# Top.net
KiCad netlist of a schematic drawn in Altium Designer
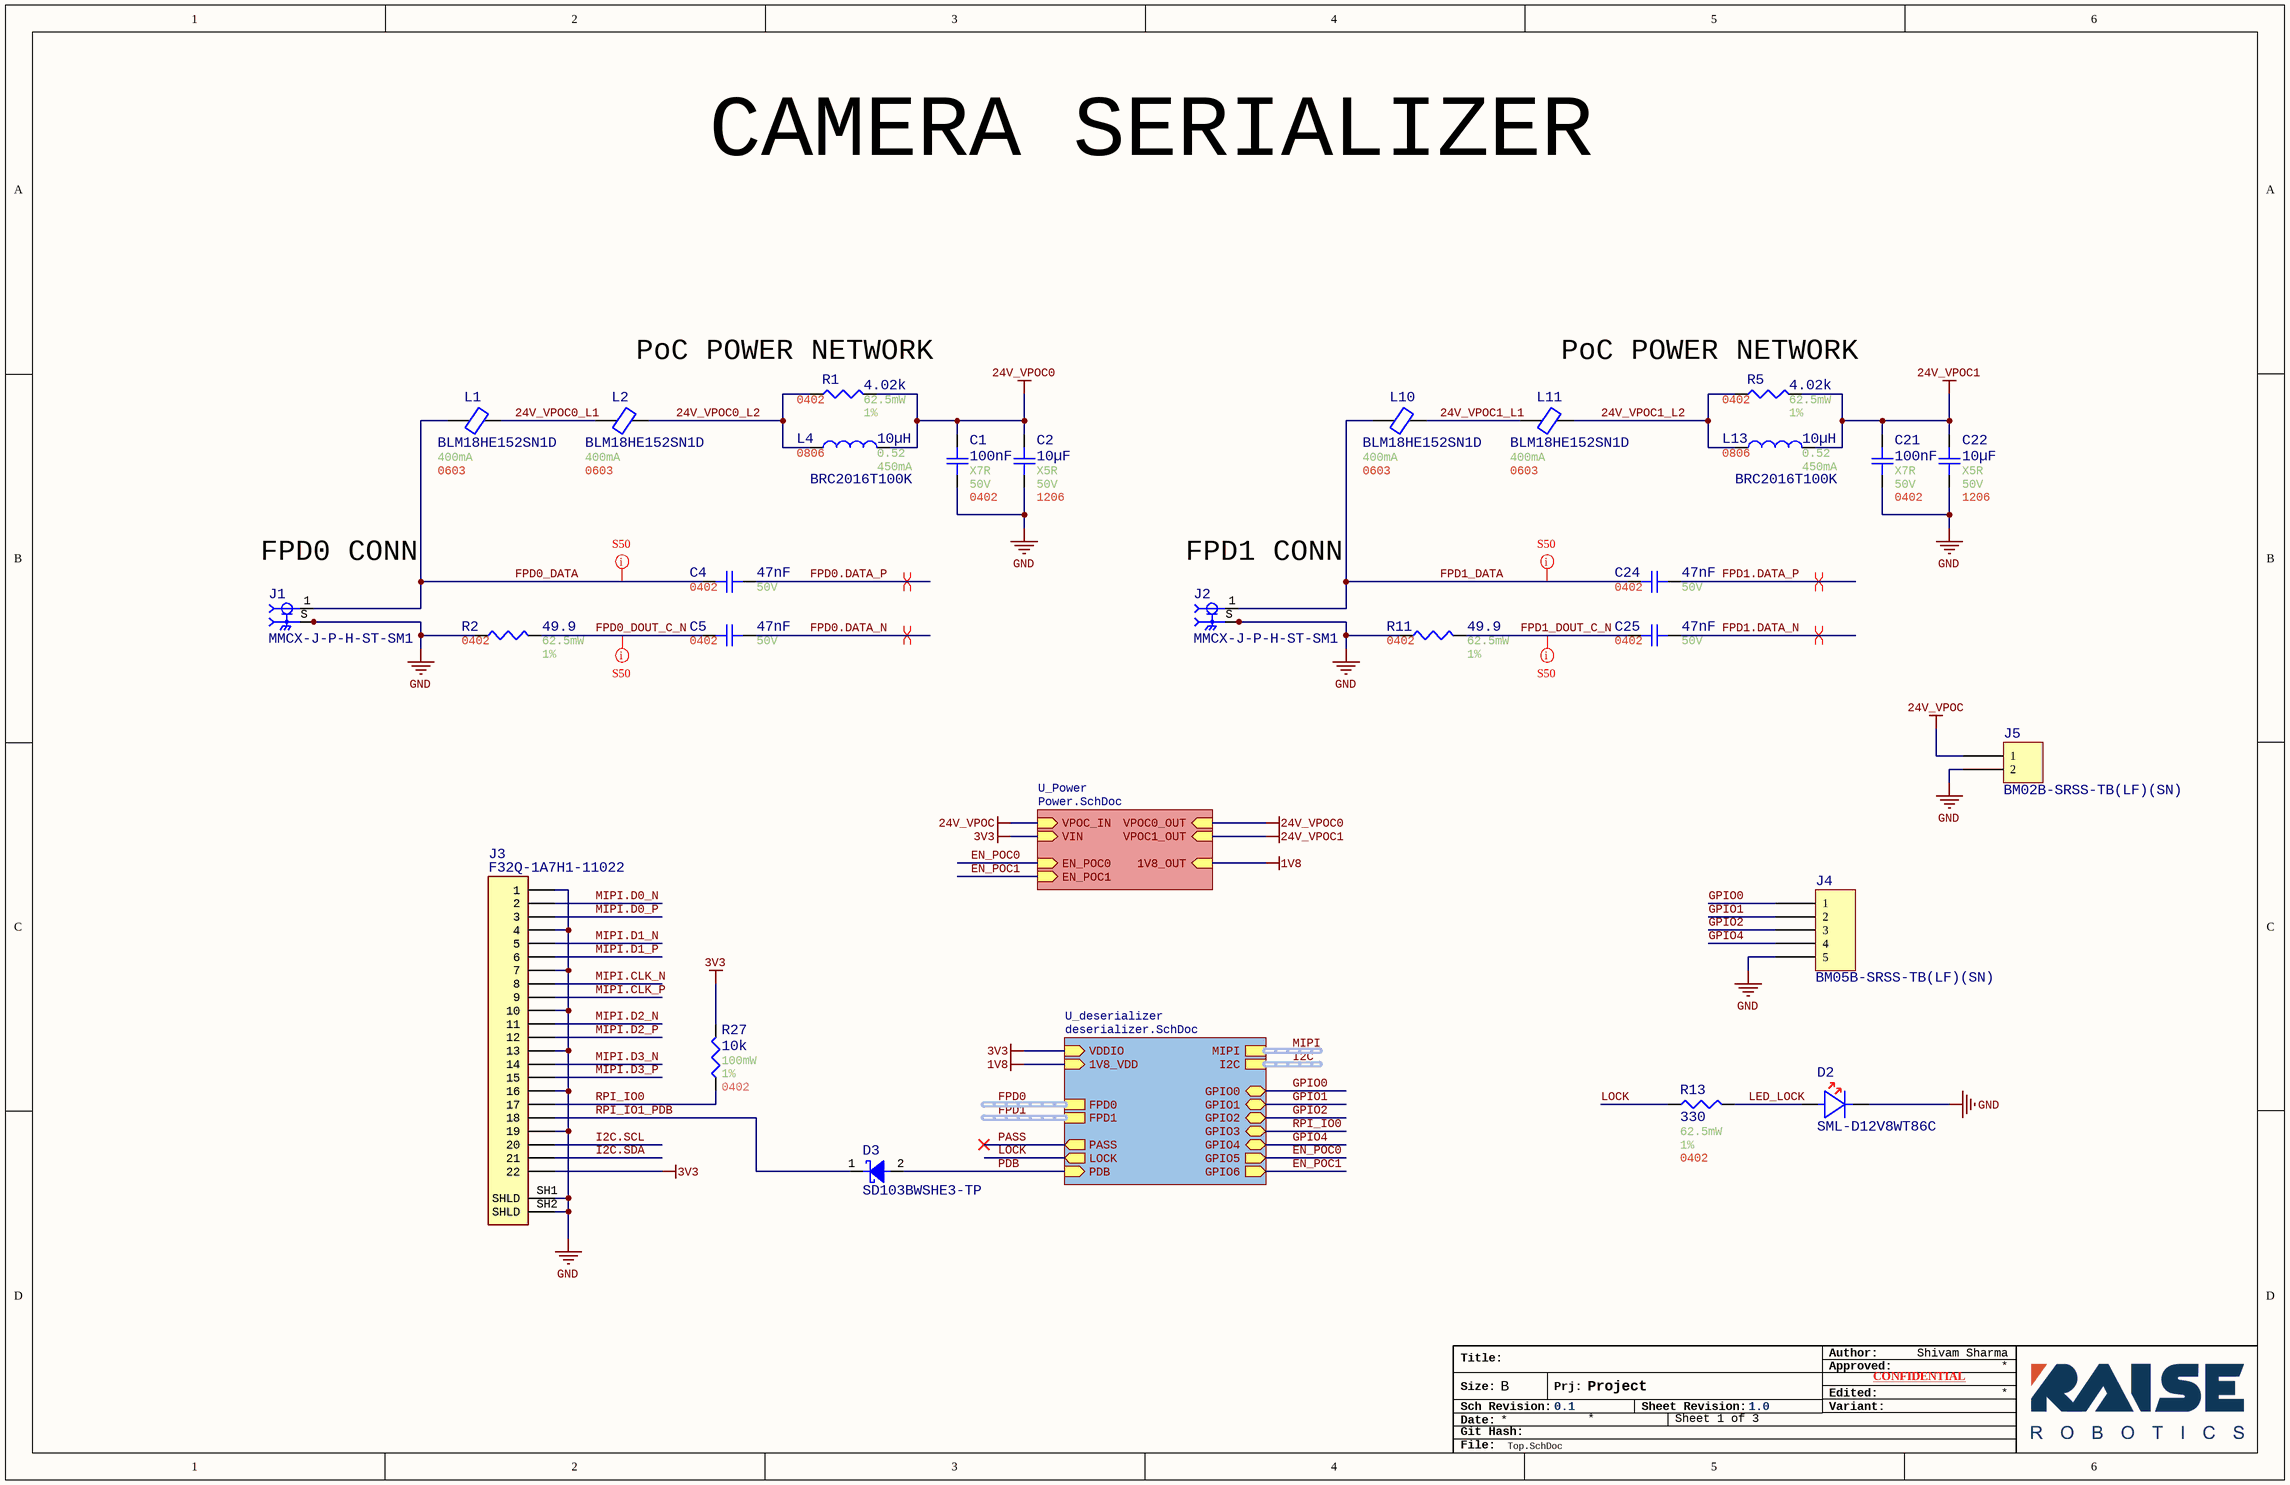
[diagram p0: Top.SchDoc]

(export (version "E")
  (design (tool "Eeschema 10.0.6"))
  (components
    (comp (ref "C1")
      (value "100nF")
      (footprint "Generic 0402 capacitor")
      (fields
        (field (name "TEMPERATURE COEFFICIENT") "X7R")
        (field (name "VOLTAGE RATING") "50V")
        (field (name "CASE/PACKAGE") "0402")
        (field (name "TOLERANCE") "10%")
        (field (name "Comment") "GRT155R71H104KE01D")
      )
      (libsource (lib "Raise Robotics") (part "Unpolarized Capacitor"))
    )
    (comp (ref "C2")
      (value "10µF")
      (footprint "Generic 1206 Capacitor")
      (fields
        (field (name "TEMPERATURE COEFFICIENT") "X5R")
        (field (name "VOLTAGE RATING") "50V")
        (field (name "CASE/PACKAGE") "1206")
        (field (name "TOLERANCE") "20%")
        (field (name "Comment") "CL31A106MBHNNNE")
      )
      (libsource (lib "Raise Robotics") (part "Unpolarized Capacitor"))
    )
    (comp (ref "C4")
      (value "47nF")
      (footprint "Generic 0402 capacitor")
      (description "50V 47nF X7R ±10% 0402 Multilayer Ceramic Capacitors MLCC - SMD/SMT ROHS")
      (fields
        (field (name "VOLTAGE RATING") "50V")
        (field (name "CASE/PACKAGE") "0402")
        (field (name "TOLERANCE") "10%")
        (field (name "Comment") "GRM155R71H473KE14D")
      )
      (libsource (lib "Raise Robotics") (part "Unpolarized Capacitor"))
    )
    (comp (ref "C5")
      (value "47nF")
      (footprint "Generic 0402 capacitor")
      (description "50V 47nF X7R ±10% 0402 Multilayer Ceramic Capacitors MLCC - SMD/SMT ROHS")
      (fields
        (field (name "VOLTAGE RATING") "50V")
        (field (name "CASE/PACKAGE") "0402")
        (field (name "TOLERANCE") "10%")
        (field (name "Comment") "GRM155R71H473KE14D")
      )
      (libsource (lib "Raise Robotics") (part "Unpolarized Capacitor"))
    )
    (comp (ref "C21")
      (value "100nF")
      (footprint "Generic 0402 capacitor")
      (fields
        (field (name "TEMPERATURE COEFFICIENT") "X7R")
        (field (name "VOLTAGE RATING") "50V")
        (field (name "CASE/PACKAGE") "0402")
        (field (name "TOLERANCE") "10%")
        (field (name "Comment") "GRT155R71H104KE01D")
      )
      (libsource (lib "Raise Robotics") (part "Unpolarized Capacitor"))
    )
    (comp (ref "C22")
      (value "10µF")
      (footprint "Generic 1206 Capacitor")
      (fields
        (field (name "TEMPERATURE COEFFICIENT") "X5R")
        (field (name "VOLTAGE RATING") "50V")
        (field (name "CASE/PACKAGE") "1206")
        (field (name "TOLERANCE") "20%")
        (field (name "Comment") "CL31A106MBHNNNE")
      )
      (libsource (lib "Raise Robotics") (part "Unpolarized Capacitor"))
    )
    (comp (ref "C24")
      (value "47nF")
      (footprint "Generic 0402 capacitor")
      (description "50V 47nF X7R ±10% 0402 Multilayer Ceramic Capacitors MLCC - SMD/SMT ROHS")
      (fields
        (field (name "VOLTAGE RATING") "50V")
        (field (name "CASE/PACKAGE") "0402")
        (field (name "TOLERANCE") "10%")
        (field (name "Comment") "GRM155R71H473KE14D")
      )
      (libsource (lib "Raise Robotics") (part "Unpolarized Capacitor"))
    )
    (comp (ref "C25")
      (value "47nF")
      (footprint "Generic 0402 capacitor")
      (description "50V 47nF X7R ±10% 0402 Multilayer Ceramic Capacitors MLCC - SMD/SMT ROHS")
      (fields
        (field (name "VOLTAGE RATING") "50V")
        (field (name "CASE/PACKAGE") "0402")
        (field (name "TOLERANCE") "10%")
        (field (name "Comment") "GRM155R71H473KE14D")
      )
      (libsource (lib "Raise Robotics") (part "Unpolarized Capacitor"))
    )
    (comp (ref "D2")
      (value "SML-D12V8WT86C")
      (footprint "FP-SML-D12-MFG")
      (description "Red 630nm LED Indication - Discrete 2.2V 0603 (1608 Metric)")
      (libsource (lib "Raise Robotics") (part "LED Red"))
    )
    (comp (ref "D3")
      (value "SD103BWSHE3-TP")
      (footprint "SOD-323")
      (description "Rectifier Diode, Schottky, 1 Phase, 1 Element, 0.35A, 30V V(RRM), Silicon")
      (libsource (lib "Raise Robotics") (part "Generic 2 pin Diode"))
    )
    (comp (ref "J1")
      (value "MMCX-J-P-H-ST-SM1")
      (footprint "MMCX-J-P-H-ST-SM1")
      (description "RF / Coaxial Connector, MMCX Coaxial, Straight Jack, Surface Mount Vertical, 50 ohm")
      (fields (field (name "MANUFACTURER") "Samtec"))
      (libsource (lib "Raise Robotics") (part "RF 1pin + 4 shield"))
    )
    (comp (ref "J2")
      (value "MMCX-J-P-H-ST-SM1")
      (footprint "MMCX-J-P-H-ST-SM1")
      (description "RF / Coaxial Connector, MMCX Coaxial, Straight Jack, Surface Mount Vertical, 50 ohm")
      (fields (field (name "MANUFACTURER") "Samtec"))
      (libsource (lib "Raise Robotics") (part "RF 1pin + 4 shield"))
    )
    (comp (ref "J3")
      (value "F32Q-1A7H1-11022")
      (footprint "F32Q-1A7H1-11022")
      (description "FPC/FFC Connector Socket 22 Position 0.5mm Top Contact Solder Right Angle Surface Mount T/R")
      (fields (field (name "MANUFACTURER") "Amphenol"))
      (libsource (lib "Raise Robotics") (part "F32Q-1A7H1-11022"))
    )
    (comp (ref "J4")
      (value "BM05B-SRSS-TB(LF)(SN)")
      (footprint "JST BM05B-SRSS-TB")
      (description "CONN HEADER SMD 5POS 1MM")
      (fields (field (name "MANUFACTURER") "JST Sales America Inc."))
      (libsource (lib "Celestial Altium Library - altium_library") (part "5 Pin"))
    )
    (comp (ref "J5")
      (value "BM02B-SRSS-TB(LF)(SN)")
      (footprint "JST BM02B-SRSS-TB")
      (description "CONN HEADER SMD 2POS 1MM")
      (fields (field (name "MANUFACTURER") "JST Sales America Inc."))
      (libsource (lib "Celestial Altium Library - altium_library") (part "2 Pin"))
    )
    (comp (ref "L1")
      (value "BLM18HE152SN1D")
      (footprint "0603_1.6x0.8x0.8mm_IND")
      (description "Ferrite Beads Multi-Layer 1.5KOhm 25% 100MHz 500mA 500mOhm DCR 0603 T/R")
      (fields
        (field (name "CURRENT RATING") "400mA")
        (field (name "CASE/PACKAGE") "0603")
        (field (name "TOLERANCE") "25%")
      )
      (libsource (lib "Raise Robotics") (part "Generic 2 pin ferrite bead"))
    )
    (comp (ref "L2")
      (value "BLM18HE152SN1D")
      (footprint "0603_1.6x0.8x0.8mm_IND")
      (description "Ferrite Beads Multi-Layer 1.5KOhm 25% 100MHz 500mA 500mOhm DCR 0603 T/R")
      (fields
        (field (name "CURRENT RATING") "400mA")
        (field (name "CASE/PACKAGE") "0603")
        (field (name "TOLERANCE") "25%")
      )
      (libsource (lib "Raise Robotics") (part "Generic 2 pin ferrite bead"))
    )
    (comp (ref "L4")
      (value "BRC2016T100K")
      (footprint "0805_2.0x1.6x1.6mm_IND")
      (description "IND 10UH 20% 3.1A SHD")
      (fields
        (field (name "DCR") "0.52")
        (field (name "CURRENT RATING") "450mA")
        (field (name "CASE/PACKAGE") "0806")
        (field (name "ALTIUM_VALUE") "10µH")
        (field (name "TOLERANCE") "10%")
      )
      (libsource (lib "Raise Robotics") (part "Generic 2 pin inductor"))
    )
    (comp (ref "L10")
      (value "BLM18HE152SN1D")
      (footprint "0603_1.6x0.8x0.8mm_IND")
      (description "Ferrite Beads Multi-Layer 1.5KOhm 25% 100MHz 500mA 500mOhm DCR 0603 T/R")
      (fields
        (field (name "CURRENT RATING") "400mA")
        (field (name "CASE/PACKAGE") "0603")
        (field (name "TOLERANCE") "25%")
      )
      (libsource (lib "Raise Robotics") (part "Generic 2 pin ferrite bead"))
    )
    (comp (ref "L11")
      (value "BLM18HE152SN1D")
      (footprint "0603_1.6x0.8x0.8mm_IND")
      (description "Ferrite Beads Multi-Layer 1.5KOhm 25% 100MHz 500mA 500mOhm DCR 0603 T/R")
      (fields
        (field (name "CURRENT RATING") "400mA")
        (field (name "CASE/PACKAGE") "0603")
        (field (name "TOLERANCE") "25%")
      )
      (libsource (lib "Raise Robotics") (part "Generic 2 pin ferrite bead"))
    )
    (comp (ref "L13")
      (value "BRC2016T100K")
      (footprint "0805_2.0x1.6x1.6mm_IND")
      (description "IND 10UH 20% 3.1A SHD")
      (fields
        (field (name "DCR") "0.52")
        (field (name "CURRENT RATING") "450mA")
        (field (name "CASE/PACKAGE") "0806")
        (field (name "ALTIUM_VALUE") "10µH")
        (field (name "TOLERANCE") "10%")
      )
      (libsource (lib "Raise Robotics") (part "Generic 2 pin inductor"))
    )
    (comp (ref "R1")
      (value "4.02k")
      (footprint "Generic 0402 Resistor")
      (description "Fixed Resistor, Metal Glaze/Thick Film, 0.063W, 4020ohm, 50V, 1% +/-Tol, Surface Mount, 0402")
      (fields
        (field (name "POWER") "62.5mW")
        (field (name "TOLERANCE") "1%")
        (field (name "CASE/PACKAGE") "0402")
        (field (name "MANUFACTURER PART NUMBER") "Blank")
        (field (name "Comment") "RCA04024K02FKEDSR")
      )
      (libsource (lib "Raise Robotics") (part "Resistor"))
    )
    (comp (ref "R2")
      (value "49.9")
      (footprint "Generic 0402 Resistor")
      (description "RES, 0402, 49.9 ohm, 1%, 0.1W, AUTO")
      (fields
        (field (name "POWER") "62.5mW")
        (field (name "TOLERANCE") "1%")
        (field (name "CASE/PACKAGE") "0402")
        (field (name "MANUFACTURER PART NUMBER") "RMCA0402FT49R9-HP")
      )
      (libsource (lib "Raise Robotics") (part "Resistor"))
    )
    (comp (ref "R5")
      (value "4.02k")
      (footprint "Generic 0402 Resistor")
      (description "Fixed Resistor, Metal Glaze/Thick Film, 0.063W, 4020ohm, 50V, 1% +/-Tol, Surface Mount, 0402")
      (fields
        (field (name "POWER") "62.5mW")
        (field (name "TOLERANCE") "1%")
        (field (name "CASE/PACKAGE") "0402")
        (field (name "MANUFACTURER PART NUMBER") "Blank")
        (field (name "Comment") "RCA04024K02FKEDSR")
      )
      (libsource (lib "Raise Robotics") (part "Resistor"))
    )
    (comp (ref "R11")
      (value "49.9")
      (footprint "Generic 0402 Resistor")
      (description "RES, 0402, 49.9 ohm, 1%, 0.1W, AUTO")
      (fields
        (field (name "POWER") "62.5mW")
        (field (name "TOLERANCE") "1%")
        (field (name "CASE/PACKAGE") "0402")
        (field (name "MANUFACTURER PART NUMBER") "RMCA0402FT49R9-HP")
      )
      (libsource (lib "Raise Robotics") (part "Resistor"))
    )
    (comp (ref "R13")
      (value "330")
      (footprint "Generic 0402 Resistor")
      (description "Res Thick Film 0402 330 Ohm 1% 0.063W ±100ppm/°C Molded SMD Paper T/R")
      (fields
        (field (name "POWER") "62.5mW")
        (field (name "TOLERANCE") "1%")
        (field (name "CASE/PACKAGE") "0402")
        (field (name "Comment") "RMCF0402FT330R")
      )
      (libsource (lib "Raise Robotics") (part "Resistor"))
    )
    (comp (ref "R27")
      (value "10k")
      (footprint "Generic 0402 Resistor")
      (description "Fixed Resistor, Thin Film, 0.1W, 10000ohm, 50V, 1% +/-Tol, 100ppm/Cel, Surface Mount, 0402")
      (fields
        (field (name "POWER") "100mW")
        (field (name "TOLERANCE") "1%")
        (field (name "CASE/PACKAGE") "0402")
        (field (name "MANUFACTURER PART NUMBER") "Blank")
        (field (name "Comment") "RNCP0402FTD10K0")
      )
      (libsource (lib "Raise Robotics") (part "Resistor"))
    )
  )
  (nets
    (net (code "5") (name "/24V_VPOC0_L1") (class "Default")
      (node (ref "L1") (pin "2") (pinfunction "2_2") (pintype "passive"))
      (node (ref "L2") (pin "1") (pinfunction "1_1") (pintype "passive"))
    )
    (net (code "6") (name "/24V_VPOC0_L2") (class "Default")
      (node (ref "L2") (pin "2") (pinfunction "2_2") (pintype "passive"))
      (node (ref "L4") (pin "1") (pinfunction "1_1") (pintype "passive"))
      (node (ref "R1") (pin "1") (pinfunction "1_1") (pintype "passive"))
    )
    (net (code "7") (name "/24V_VPOC1_L1") (class "Default")
      (node (ref "L10") (pin "2") (pinfunction "2_2") (pintype "passive"))
      (node (ref "L11") (pin "1") (pinfunction "1_1") (pintype "passive"))
    )
    (net (code "8") (name "/24V_VPOC1_L2") (class "Default")
      (node (ref "L11") (pin "2") (pinfunction "2_2") (pintype "passive"))
      (node (ref "L13") (pin "1") (pinfunction "1_1") (pintype "passive"))
      (node (ref "R5") (pin "1") (pinfunction "1_1") (pintype "passive"))
    )
    (net (code "11") (name "/FPD0.DATA_N") (class "Default")
      (node (ref "C5") (pin "1") (pinfunction "1_1") (pintype "passive"))
    )
    (net (code "12") (name "/FPD0.DATA_P") (class "Default")
      (node (ref "C4") (pin "1") (pinfunction "1_1") (pintype "passive"))
    )
    (net (code "13") (name "/FPD0_DATA") (class "Default")
      (node (ref "C4") (pin "2") (pinfunction "2_2") (pintype "passive"))
      (node (ref "J1") (pin "1") (pinfunction "1_1") (pintype "passive"))
      (node (ref "L1") (pin "1") (pinfunction "1_1") (pintype "passive"))
    )
    (net (code "14") (name "/FPD0_DOUT_C_N") (class "Default")
      (node (ref "C5") (pin "2") (pinfunction "2_2") (pintype "passive"))
      (node (ref "R2") (pin "2") (pinfunction "2_2") (pintype "passive"))
    )
    (net (code "15") (name "/FPD1.DATA_N") (class "Default")
      (node (ref "C25") (pin "1") (pinfunction "1_1") (pintype "passive"))
    )
    (net (code "16") (name "/FPD1.DATA_P") (class "Default")
      (node (ref "C24") (pin "1") (pinfunction "1_1") (pintype "passive"))
    )
    (net (code "17") (name "/FPD1_DATA") (class "Default")
      (node (ref "C24") (pin "2") (pinfunction "2_2") (pintype "passive"))
      (node (ref "J2") (pin "1") (pinfunction "1_1") (pintype "passive"))
      (node (ref "L10") (pin "1") (pinfunction "1_1") (pintype "passive"))
    )
    (net (code "18") (name "/FPD1_DOUT_C_N") (class "Default")
      (node (ref "C25") (pin "2") (pinfunction "2_2") (pintype "passive"))
      (node (ref "R11") (pin "2") (pinfunction "2_2") (pintype "passive"))
    )
    (net (code "19") (name "/GPIO0") (class "Default")
      (node (ref "J4") (pin "1") (pinfunction "1_1") (pintype "passive"))
    )
    (net (code "20") (name "/GPIO1") (class "Default")
      (node (ref "J4") (pin "2") (pinfunction "2_2") (pintype "passive"))
    )
    (net (code "21") (name "/GPIO2") (class "Default")
      (node (ref "J4") (pin "3") (pinfunction "3_3") (pintype "passive"))
    )
    (net (code "22") (name "/GPIO4") (class "Default")
      (node (ref "J4") (pin "4") (pinfunction "4_4") (pintype "passive"))
    )
    (net (code "23") (name "/I2C.SCL") (class "Default")
      (node (ref "J3") (pin "20") (pinfunction "20_20") (pintype "passive"))
    )
    (net (code "24") (name "/I2C.SDA") (class "Default")
      (node (ref "J3") (pin "21") (pinfunction "21_21") (pintype "passive"))
    )
    (net (code "25") (name "/LED_LOCK") (class "Default")
      (node (ref "D2") (pin "2") (pinfunction "A_2") (pintype "passive"))
      (node (ref "R13") (pin "2") (pinfunction "2_2") (pintype "passive"))
    )
    (net (code "26") (name "/LOCK") (class "Default")
      (node (ref "R13") (pin "1") (pinfunction "1_1") (pintype "passive"))
    )
    (net (code "27") (name "/MIPI.CLK_N") (class "Default")
      (node (ref "J3") (pin "8") (pinfunction "8_8") (pintype "passive"))
    )
    (net (code "28") (name "/MIPI.CLK_P") (class "Default")
      (node (ref "J3") (pin "9") (pinfunction "9_9") (pintype "passive"))
    )
    (net (code "29") (name "/MIPI.D0_N") (class "Default")
      (node (ref "J3") (pin "2") (pinfunction "2_2") (pintype "passive"))
    )
    (net (code "30") (name "/MIPI.D0_P") (class "Default")
      (node (ref "J3") (pin "3") (pinfunction "3_3") (pintype "passive"))
    )
    (net (code "31") (name "/MIPI.D1_N") (class "Default")
      (node (ref "J3") (pin "5") (pinfunction "5_5") (pintype "passive"))
    )
    (net (code "32") (name "/MIPI.D1_P") (class "Default")
      (node (ref "J3") (pin "6") (pinfunction "6_6") (pintype "passive"))
    )
    (net (code "33") (name "/MIPI.D2_N") (class "Default")
      (node (ref "J3") (pin "11") (pinfunction "11_11") (pintype "passive"))
    )
    (net (code "34") (name "/MIPI.D2_P") (class "Default")
      (node (ref "J3") (pin "12") (pinfunction "12_12") (pintype "passive"))
    )
    (net (code "35") (name "/MIPI.D3_N") (class "Default")
      (node (ref "J3") (pin "14") (pinfunction "14_14") (pintype "passive"))
    )
    (net (code "36") (name "/MIPI.D3_P") (class "Default")
      (node (ref "J3") (pin "15") (pinfunction "15_15") (pintype "passive"))
    )
    (net (code "38") (name "/PDB") (class "Default")
      (node (ref "D3") (pin "2") (pinfunction "A_2") (pintype "passive"))
    )
    (net (code "39") (name "/RPI_IO0") (class "Default")
      (node (ref "J3") (pin "17") (pinfunction "17_17") (pintype "passive"))
      (node (ref "R27") (pin "1") (pinfunction "1_1") (pintype "passive"))
    )
    (net (code "40") (name "/RPI_IO1_PDB") (class "Default")
      (node (ref "D3") (pin "1") (pinfunction "C_1") (pintype "passive"))
      (node (ref "J3") (pin "18") (pinfunction "18_18") (pintype "passive"))
    )
    (net (code "46") (name "3V3") (class "Default")
      (node (ref "J3") (pin "22") (pinfunction "22_22") (pintype "passive"))
      (node (ref "R27") (pin "2") (pinfunction "2_2") (pintype "passive"))
    )
    (net (code "47") (name "24V_VPOC") (class "Default")
      (node (ref "J5") (pin "1") (pinfunction "1_1") (pintype "passive"))
    )
    (net (code "48") (name "24V_VPOC0") (class "Default")
      (node (ref "C1") (pin "2") (pinfunction "2_2") (pintype "passive"))
      (node (ref "C2") (pin "2") (pinfunction "2_2") (pintype "passive"))
      (node (ref "L4") (pin "2") (pinfunction "2_2") (pintype "passive"))
      (node (ref "R1") (pin "2") (pinfunction "2_2") (pintype "passive"))
    )
    (net (code "49") (name "24V_VPOC1") (class "Default")
      (node (ref "C21") (pin "2") (pinfunction "2_2") (pintype "passive"))
      (node (ref "C22") (pin "2") (pinfunction "2_2") (pintype "passive"))
      (node (ref "L13") (pin "2") (pinfunction "2_2") (pintype "passive"))
      (node (ref "R5") (pin "2") (pinfunction "2_2") (pintype "passive"))
    )
    (net (code "50") (name "GND") (class "Default")
      (node (ref "C1") (pin "1") (pinfunction "1_1") (pintype "passive"))
      (node (ref "C2") (pin "1") (pinfunction "1_1") (pintype "passive"))
      (node (ref "C21") (pin "1") (pinfunction "1_1") (pintype "passive"))
      (node (ref "C22") (pin "1") (pinfunction "1_1") (pintype "passive"))
      (node (ref "D2") (pin "1") (pinfunction "C_1") (pintype "passive"))
      (node (ref "J1") (pin "S1") (pinfunction "2_S1") (pintype "passive"))
      (node (ref "J1") (pin "S2") (pinfunction "2_S2") (pintype "passive"))
      (node (ref "J1") (pin "S3") (pinfunction "2_S3") (pintype "passive"))
      (node (ref "J1") (pin "S4") (pinfunction "2_S4") (pintype "passive"))
      (node (ref "J2") (pin "S1") (pinfunction "2_S1") (pintype "passive"))
      (node (ref "J2") (pin "S2") (pinfunction "2_S2") (pintype "passive"))
      (node (ref "J2") (pin "S3") (pinfunction "2_S3") (pintype "passive"))
      (node (ref "J2") (pin "S4") (pinfunction "2_S4") (pintype "passive"))
      (node (ref "J3") (pin "1") (pinfunction "1_1") (pintype "passive"))
      (node (ref "J3") (pin "10") (pinfunction "10_10") (pintype "passive"))
      (node (ref "J3") (pin "13") (pinfunction "13_13") (pintype "passive"))
      (node (ref "J3") (pin "16") (pinfunction "16_16") (pintype "passive"))
      (node (ref "J3") (pin "19") (pinfunction "19_19") (pintype "passive"))
      (node (ref "J3") (pin "4") (pinfunction "4_4") (pintype "passive"))
      (node (ref "J3") (pin "7") (pinfunction "7_7") (pintype "passive"))
      (node (ref "J3") (pin "SH1") (pinfunction "SHLD_SH1") (pintype "passive"))
      (node (ref "J3") (pin "SH2") (pinfunction "SHLD_SH2") (pintype "passive"))
      (node (ref "J4") (pin "5") (pinfunction "5_5") (pintype "passive"))
      (node (ref "J5") (pin "2") (pinfunction "2_2") (pintype "passive"))
      (node (ref "R11") (pin "1") (pinfunction "1_1") (pintype "passive"))
      (node (ref "R2") (pin "1") (pinfunction "1_1") (pintype "passive"))
    )
  )
)
